# GSM_M95.net
KiCad netlist of a schematic drawn in EAGLE
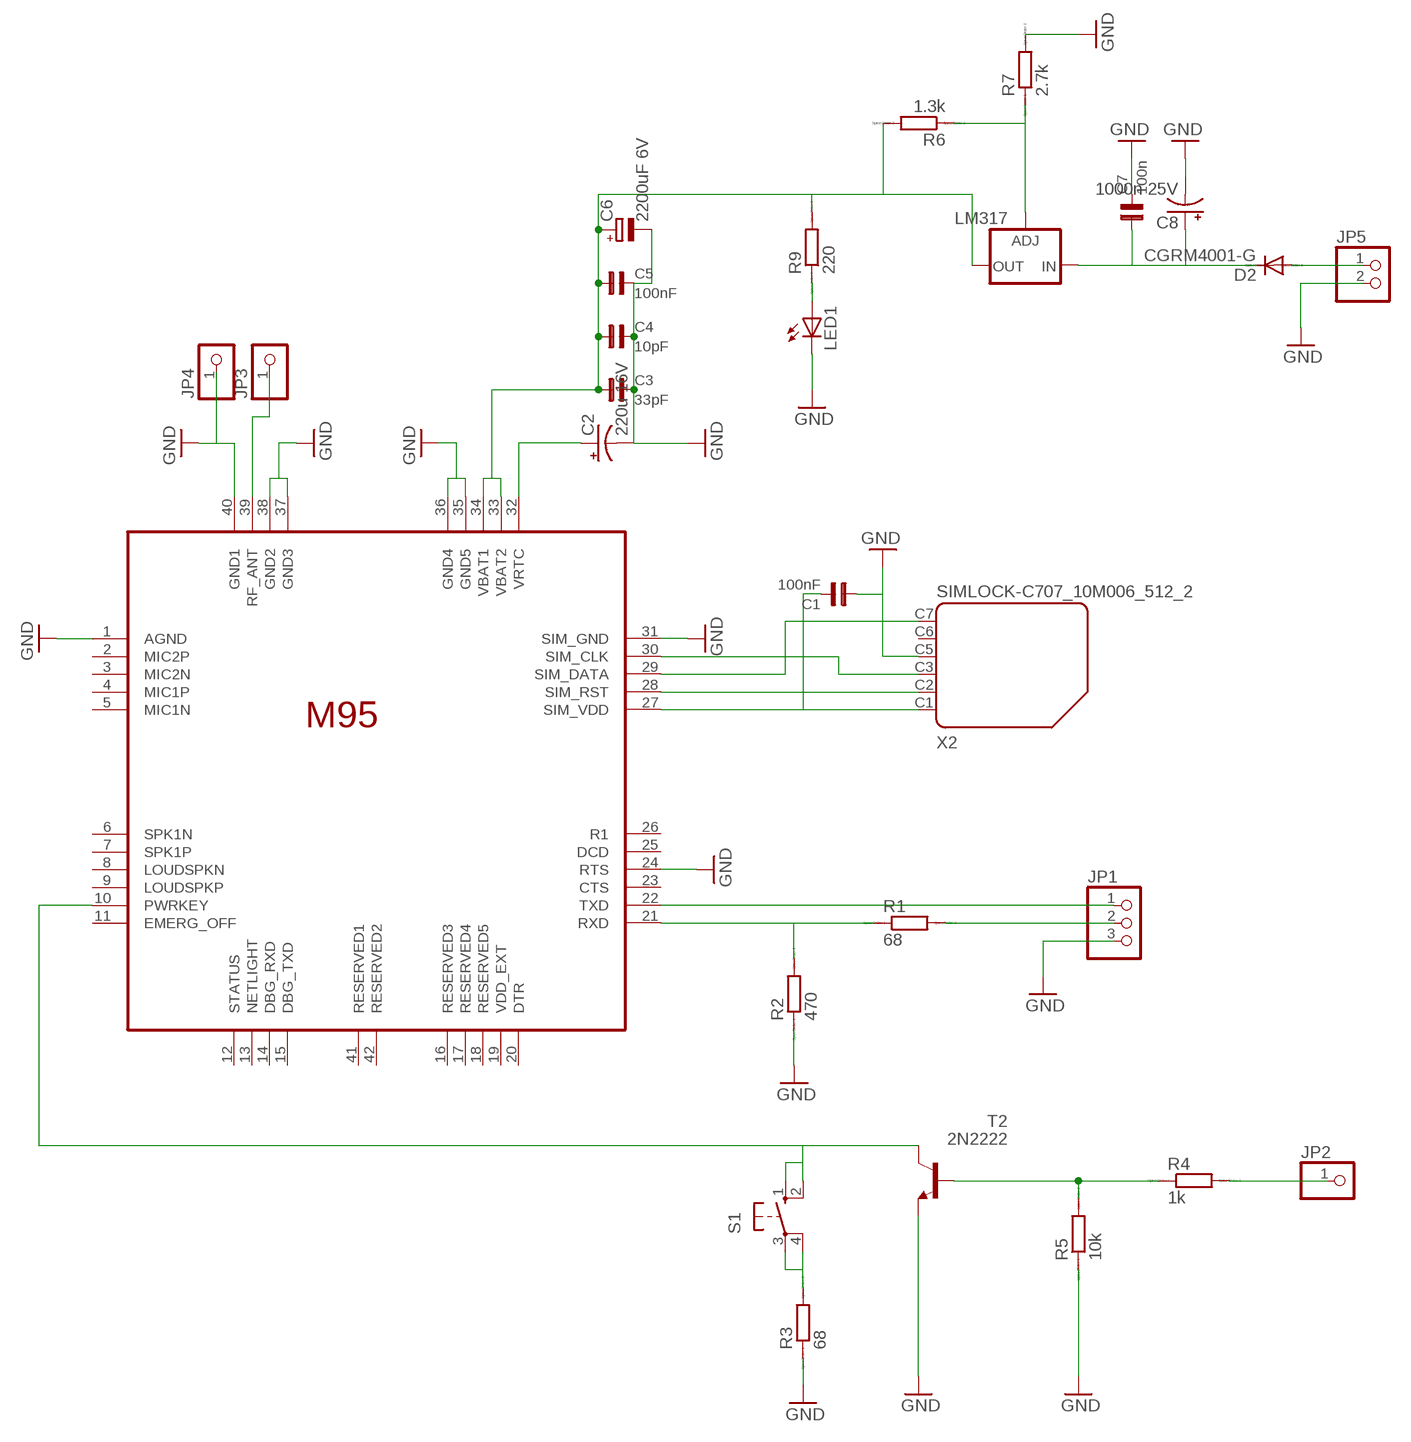
[diagram p0: schematic, sheet 1]

(export (version "E")
  (design (tool "Eeschema 10.0.6"))
  (components
    (comp (ref "C1")
      (value "100nF")
      (footprint "eagle-import:1206")
      (libsource (lib "eagle-import") (part "C1206"))
    )
    (comp (ref "C2")
      (value "220u 16V")
      (footprint "eagle-import:UD-6,3X7,7_NICHICON")
      (libsource (lib "eagle-import") (part "CPOL-USUD-6,3X7,7"))
    )
    (comp (ref "C3")
      (value "33pF")
      (footprint "eagle-import:1206")
      (libsource (lib "eagle-import") (part "C1206"))
    )
    (comp (ref "C4")
      (value "10pF")
      (footprint "eagle-import:1206")
      (libsource (lib "eagle-import") (part "C1206"))
    )
    (comp (ref "C5")
      (value "100nF")
      (footprint "eagle-import:1206")
      (libsource (lib "eagle-import") (part "C1206"))
    )
    (comp (ref "C6")
      (value "2200uF 6V")
      (footprint "eagle-import:E5-10,5")
      (libsource (lib "eagle-import") (part "CPOL-EUE5-10.5"))
    )
    (comp (ref "C7")
      (value "100n")
      (footprint "eagle-import:1206")
      (libsource (lib "eagle-import") (part "C1206"))
    )
    (comp (ref "C8")
      (value "1000n 25V")
      (footprint "eagle-import:E5-13")
      (libsource (lib "eagle-import") (part "CPOL-USE5-13"))
    )
    (comp (ref "D2")
      (value "CGRM4001-G")
      (footprint "eagle-import:SOD-123_MINI-SMA")
      (libsource (lib "eagle-import") (part "CGRM400-G1"))
    )
    (comp (ref "JP1")
      (value "PINHD-1X3")
      (footprint "eagle-import:1X03")
      (libsource (lib "eagle-import") (part "PINHD-1X3"))
    )
    (comp (ref "JP2")
      (value "PINHD-1X1")
      (footprint "eagle-import:1X01")
      (libsource (lib "eagle-import") (part "PINHD-1X1"))
    )
    (comp (ref "JP3")
      (value "PINHD-1X1")
      (footprint "eagle-import:1X01")
      (libsource (lib "eagle-import") (part "PINHD-1X1"))
    )
    (comp (ref "JP4")
      (value "PINHD-1X1")
      (footprint "eagle-import:1X01")
      (libsource (lib "eagle-import") (part "PINHD-1X1"))
    )
    (comp (ref "JP5")
      (value "PINHD-1X2")
      (footprint "eagle-import:1X02")
      (libsource (lib "eagle-import") (part "PINHD-1X2"))
    )
    (comp (ref "LED1")
      (value "LED3MM")
      (footprint "eagle-import:LED3MM")
      (libsource (lib "eagle-import") (part "LED3MM"))
    )
    (comp (ref "LM317")
      (value "LM317TL")
      (footprint "eagle-import:317TL")
      (libsource (lib "eagle-import") (part "LM317TL"))
    )
    (comp (ref "M95")
      (value "M95_HD_V1.0")
      (footprint "eagle-import:M95")
      (libsource (lib "eagle-import") (part "M95_HD_V1.0"))
    )
    (comp (ref "R1")
      (value "68")
      (footprint "eagle-import:R1206W")
      (libsource (lib "eagle-import") (part "R-EU_R1206W"))
    )
    (comp (ref "R2")
      (value "470")
      (footprint "eagle-import:R1206W")
      (libsource (lib "eagle-import") (part "R-EU_R1206W"))
    )
    (comp (ref "R3")
      (value "68")
      (footprint "eagle-import:R1206W")
      (libsource (lib "eagle-import") (part "R-EU_R1206W"))
    )
    (comp (ref "R4")
      (value "1k")
      (footprint "eagle-import:R1206W")
      (libsource (lib "eagle-import") (part "R-EU_R1206W"))
    )
    (comp (ref "R5")
      (value "10k")
      (footprint "eagle-import:R1206W")
      (libsource (lib "eagle-import") (part "R-EU_R1206W"))
    )
    (comp (ref "R6")
      (value "1.3k")
      (footprint "eagle-import:R1206W")
      (libsource (lib "eagle-import") (part "R-EU_R1206W"))
    )
    (comp (ref "R7")
      (value "2.7k")
      (footprint "eagle-import:R1206W")
      (libsource (lib "eagle-import") (part "R-EU_R1206W"))
    )
    (comp (ref "R9")
      (value "220")
      (footprint "eagle-import:R0805")
      (libsource (lib "eagle-import") (part "R-EU_R0805"))
    )
    (comp (ref "S1")
      (value "10-XX")
      (footprint "eagle-import:B3F-10XX")
      (fields (field (name "MPN") "B3F-1000"))
      (libsource (lib "eagle-import") (part "10-XX"))
    )
    (comp (ref "T2")
      (value "2N2222")
      (footprint "eagle-import:TO92-EBC")
      (libsource (lib "eagle-import") (part "-NPN-TO92-EBC2N2222"))
    )
    (comp (ref "X2")
      (value "SIMLOCK-C707_10M006_512_2")
      (footprint "eagle-import:C707_10M006_512_2")
      (libsource (lib "eagle-import") (part "SIMLOCK-C707_10M006_512_2"))
    )
  )
  (nets
    (net (code "1") (name "GND") (class "Default")
      (node (ref "C1") (pin "1") (pinfunction "1_1") (pintype "passive"))
      (node (ref "C2") (pin "-") (pinfunction "-_-") (pintype "passive"))
      (node (ref "C3") (pin "2") (pinfunction "2_2") (pintype "passive"))
      (node (ref "C4") (pin "2") (pinfunction "2_2") (pintype "passive"))
      (node (ref "C5") (pin "2") (pinfunction "2_2") (pintype "passive"))
      (node (ref "C6") (pin "-") (pinfunction "-_-") (pintype "passive"))
      (node (ref "C7") (pin "2") (pinfunction "2_2") (pintype "passive"))
      (node (ref "C8") (pin "-") (pinfunction "-_-") (pintype "passive"))
      (node (ref "JP1") (pin "3") (pinfunction "3_3") (pintype "passive"))
      (node (ref "JP4") (pin "1") (pinfunction "1_1") (pintype "passive"))
      (node (ref "JP5") (pin "2") (pinfunction "2_2") (pintype "passive"))
      (node (ref "LED1") (pin "K") (pinfunction "C_K") (pintype "passive"))
      (node (ref "M95") (pin "1") (pinfunction "AGND_1") (pintype "passive"))
      (node (ref "M95") (pin "24") (pinfunction "RTS_24") (pintype "passive"))
      (node (ref "M95") (pin "31") (pinfunction "SIM_GND_31") (pintype "passive"))
      (node (ref "M95") (pin "35") (pinfunction "GND5_35") (pintype "passive"))
      (node (ref "M95") (pin "36") (pinfunction "GND4_36") (pintype "passive"))
      (node (ref "M95") (pin "37") (pinfunction "GND3_37") (pintype "passive"))
      (node (ref "M95") (pin "38") (pinfunction "GND2_38") (pintype "passive"))
      (node (ref "M95") (pin "40") (pinfunction "GND1_40") (pintype "passive"))
      (node (ref "R2") (pin "1") (pinfunction "1_1") (pintype "passive"))
      (node (ref "R3") (pin "1") (pinfunction "1_1") (pintype "passive"))
      (node (ref "R5") (pin "1") (pinfunction "1_1") (pintype "passive"))
      (node (ref "R7") (pin "2") (pinfunction "2_2") (pintype "passive"))
      (node (ref "T2") (pin "E") (pinfunction "E_E") (pintype "passive"))
      (node (ref "X2") (pin "C5") (pinfunction "4_C5") (pintype "passive"))
    )
    (net (code "2") (name "Net-(D2-PadA)") (class "Default")
      (node (ref "D2") (pin "A") (pinfunction "A_A") (pintype "passive"))
      (node (ref "JP5") (pin "1") (pinfunction "1_1") (pintype "passive"))
    )
    (net (code "3") (name "Net-(JP1-Pad2)") (class "Default")
      (node (ref "JP1") (pin "2") (pinfunction "2_2") (pintype "passive"))
      (node (ref "R1") (pin "2") (pinfunction "2_2") (pintype "passive"))
    )
    (net (code "4") (name "Net-(JP2-Pad1)") (class "Default")
      (node (ref "JP2") (pin "1") (pinfunction "1_1") (pintype "passive"))
      (node (ref "R4") (pin "2") (pinfunction "2_2") (pintype "passive"))
    )
    (net (code "5") (name "Net-(LED1-PadA)") (class "Default")
      (node (ref "LED1") (pin "A") (pinfunction "A_A") (pintype "passive"))
      (node (ref "R9") (pin "1") (pinfunction "1_1") (pintype "passive"))
    )
    (net (code "6") (name "Net-(LM317-ADJ)") (class "Default")
      (node (ref "LM317") (pin "1") (pinfunction "ADJ_1") (pintype "input"))
      (node (ref "R6") (pin "1") (pinfunction "1_1") (pintype "passive"))
      (node (ref "R7") (pin "1") (pinfunction "1_1") (pintype "passive"))
    )
    (net (code "7") (name "Net-(LM317-IN)") (class "Default")
      (node (ref "C7") (pin "1") (pinfunction "1_1") (pintype "passive"))
      (node (ref "C8") (pin "+") (pinfunction "+_+") (pintype "passive"))
      (node (ref "D2") (pin "C") (pinfunction "C_C") (pintype "passive"))
      (node (ref "LM317") (pin "3") (pinfunction "IN_3") (pintype "input"))
    )
    (net (code "8") (name "Net-(LM317-OUT)") (class "Default")
      (node (ref "C3") (pin "1") (pinfunction "1_1") (pintype "passive"))
      (node (ref "C4") (pin "1") (pinfunction "1_1") (pintype "passive"))
      (node (ref "C5") (pin "1") (pinfunction "1_1") (pintype "passive"))
      (node (ref "C6") (pin "+") (pinfunction "+_+") (pintype "passive"))
      (node (ref "LM317") (pin "2") (pinfunction "OUT_2") (pintype "passive"))
      (node (ref "M95") (pin "33") (pinfunction "VBAT2_33") (pintype "passive"))
      (node (ref "M95") (pin "34") (pinfunction "VBAT1_34") (pintype "passive"))
      (node (ref "R6") (pin "2") (pinfunction "2_2") (pintype "passive"))
      (node (ref "R9") (pin "2") (pinfunction "2_2") (pintype "passive"))
    )
    (net (code "9") (name "Net-(M95-PWRKEY)") (class "Default")
      (node (ref "M95") (pin "10") (pinfunction "PWRKEY_10") (pintype "passive"))
      (node (ref "S1") (pin "1") (pinfunction "S_1") (pintype "passive"))
      (node (ref "S1") (pin "2") (pinfunction "S1_2") (pintype "passive"))
      (node (ref "T2") (pin "C") (pinfunction "C_C") (pintype "passive"))
    )
    (net (code "10") (name "Net-(M95-RF_ANT)") (class "Default")
      (node (ref "JP3") (pin "1") (pinfunction "1_1") (pintype "passive"))
      (node (ref "M95") (pin "39") (pinfunction "RF_ANT_39") (pintype "passive"))
    )
    (net (code "11") (name "Net-(M95-RXD)") (class "Default")
      (node (ref "M95") (pin "21") (pinfunction "RXD_21") (pintype "passive"))
      (node (ref "R1") (pin "1") (pinfunction "1_1") (pintype "passive"))
      (node (ref "R2") (pin "2") (pinfunction "2_2") (pintype "passive"))
    )
    (net (code "12") (name "Net-(M95-SIM_CLK)") (class "Default")
      (node (ref "M95") (pin "30") (pinfunction "SIM_CLK_30") (pintype "passive"))
      (node (ref "X2") (pin "C3") (pinfunction "3_C3") (pintype "passive"))
    )
    (net (code "13") (name "Net-(M95-SIM_DATA)") (class "Default")
      (node (ref "M95") (pin "29") (pinfunction "SIM_DATA_29") (pintype "passive"))
      (node (ref "X2") (pin "C7") (pinfunction "6_C7") (pintype "passive"))
    )
    (net (code "14") (name "Net-(M95-SIM_RST)") (class "Default")
      (node (ref "M95") (pin "28") (pinfunction "SIM_RST_28") (pintype "passive"))
      (node (ref "X2") (pin "C2") (pinfunction "2_C2") (pintype "passive"))
    )
    (net (code "15") (name "Net-(M95-SIM_VDD)") (class "Default")
      (node (ref "C1") (pin "2") (pinfunction "2_2") (pintype "passive"))
      (node (ref "M95") (pin "27") (pinfunction "SIM_VDD_27") (pintype "passive"))
      (node (ref "X2") (pin "C1") (pinfunction "1_C1") (pintype "passive"))
    )
    (net (code "16") (name "Net-(M95-TXD)") (class "Default")
      (node (ref "JP1") (pin "1") (pinfunction "1_1") (pintype "passive"))
      (node (ref "M95") (pin "22") (pinfunction "TXD_22") (pintype "passive"))
    )
    (net (code "17") (name "Net-(M95-VRTC)") (class "Default")
      (node (ref "C2") (pin "+") (pinfunction "+_+") (pintype "passive"))
      (node (ref "M95") (pin "32") (pinfunction "VRTC_32") (pintype "passive"))
    )
    (net (code "18") (name "Net-(R4-Pad1)") (class "Default")
      (node (ref "R4") (pin "1") (pinfunction "1_1") (pintype "passive"))
      (node (ref "R5") (pin "2") (pinfunction "2_2") (pintype "passive"))
      (node (ref "T2") (pin "B") (pinfunction "B_B") (pintype "passive"))
    )
    (net (code "19") (name "Net-(S1-P)") (class "Default")
      (node (ref "R3") (pin "2") (pinfunction "2_2") (pintype "passive"))
      (node (ref "S1") (pin "3") (pinfunction "P_3") (pintype "passive"))
      (node (ref "S1") (pin "4") (pinfunction "P1_4") (pintype "passive"))
    )
    (net (code "20") (name "unconnected-(M95-CTS-Pad23)") (class "Default")
      (node (ref "M95") (pin "23") (pinfunction "CTS_23") (pintype "passive"))
    )
    (net (code "21") (name "unconnected-(M95-DBG_RXD-Pad14)") (class "Default")
      (node (ref "M95") (pin "14") (pinfunction "DBG_RXD_14") (pintype "passive"))
    )
    (net (code "22") (name "unconnected-(M95-DBG_TXD-Pad15)") (class "Default")
      (node (ref "M95") (pin "15") (pinfunction "DBG_TXD_15") (pintype "passive"))
    )
    (net (code "23") (name "unconnected-(M95-DCD-Pad25)") (class "Default")
      (node (ref "M95") (pin "25") (pinfunction "DCD_25") (pintype "passive"))
    )
    (net (code "24") (name "unconnected-(M95-DTR-Pad20)") (class "Default")
      (node (ref "M95") (pin "20") (pinfunction "DTR_20") (pintype "passive"))
    )
    (net (code "25") (name "unconnected-(M95-EMERG_OFF-Pad11)") (class "Default")
      (node (ref "M95") (pin "11") (pinfunction "EMERG_OFF_11") (pintype "passive"))
    )
    (net (code "26") (name "unconnected-(M95-LOUDSPKN-Pad8)") (class "Default")
      (node (ref "M95") (pin "8") (pinfunction "LOUDSPKN_8") (pintype "passive"))
    )
    (net (code "27") (name "unconnected-(M95-LOUDSPKP-Pad9)") (class "Default")
      (node (ref "M95") (pin "9") (pinfunction "LOUDSPKP_9") (pintype "passive"))
    )
    (net (code "28") (name "unconnected-(M95-MIC1N-Pad5)") (class "Default")
      (node (ref "M95") (pin "5") (pinfunction "MIC1N_5") (pintype "passive"))
    )
    (net (code "29") (name "unconnected-(M95-MIC1P-Pad4)") (class "Default")
      (node (ref "M95") (pin "4") (pinfunction "MIC1P_4") (pintype "passive"))
    )
    (net (code "30") (name "unconnected-(M95-MIC2N-Pad3)") (class "Default")
      (node (ref "M95") (pin "3") (pinfunction "MIC2N_3") (pintype "passive"))
    )
    (net (code "31") (name "unconnected-(M95-MIC2P-Pad2)") (class "Default")
      (node (ref "M95") (pin "2") (pinfunction "MIC2P_2") (pintype "passive"))
    )
    (net (code "32") (name "unconnected-(M95-NETLIGHT-Pad13)") (class "Default")
      (node (ref "M95") (pin "13") (pinfunction "NETLIGHT_13") (pintype "passive"))
    )
    (net (code "33") (name "unconnected-(M95-R1-Pad26)") (class "Default")
      (node (ref "M95") (pin "26") (pinfunction "R1_26") (pintype "passive"))
    )
    (net (code "34") (name "unconnected-(M95-RESERVED1-Pad41)") (class "Default")
      (node (ref "M95") (pin "41") (pinfunction "RESERVED1_41") (pintype "passive"))
    )
    (net (code "35") (name "unconnected-(M95-RESERVED2-Pad42)") (class "Default")
      (node (ref "M95") (pin "42") (pinfunction "RESERVED2_42") (pintype "passive"))
    )
    (net (code "36") (name "unconnected-(M95-RESERVED3-Pad16)") (class "Default")
      (node (ref "M95") (pin "16") (pinfunction "RESERVED3_16") (pintype "passive"))
    )
    (net (code "37") (name "unconnected-(M95-RESERVED4-Pad17)") (class "Default")
      (node (ref "M95") (pin "17") (pinfunction "RESERVED4_17") (pintype "passive"))
    )
    (net (code "38") (name "unconnected-(M95-RESERVED5-Pad18)") (class "Default")
      (node (ref "M95") (pin "18") (pinfunction "RESERVED5_18") (pintype "passive"))
    )
    (net (code "39") (name "unconnected-(M95-SPK1N-Pad6)") (class "Default")
      (node (ref "M95") (pin "6") (pinfunction "SPK1N_6") (pintype "passive"))
    )
    (net (code "40") (name "unconnected-(M95-SPK1P-Pad7)") (class "Default")
      (node (ref "M95") (pin "7") (pinfunction "SPK1P_7") (pintype "passive"))
    )
    (net (code "41") (name "unconnected-(M95-STATUS-Pad12)") (class "Default")
      (node (ref "M95") (pin "12") (pinfunction "STATUS_12") (pintype "passive"))
    )
    (net (code "42") (name "unconnected-(M95-VDD_EXT-Pad19)") (class "Default")
      (node (ref "M95") (pin "19") (pinfunction "VDD_EXT_19") (pintype "passive"))
    )
    (net (code "43") (name "unconnected-(X2-5-PadC6)") (class "Default")
      (node (ref "X2") (pin "C6") (pinfunction "5_C6") (pintype "passive"))
    )
  )
)
